# dacLayerBoard3.net
KiCad netlist of a schematic drawn in EAGLE
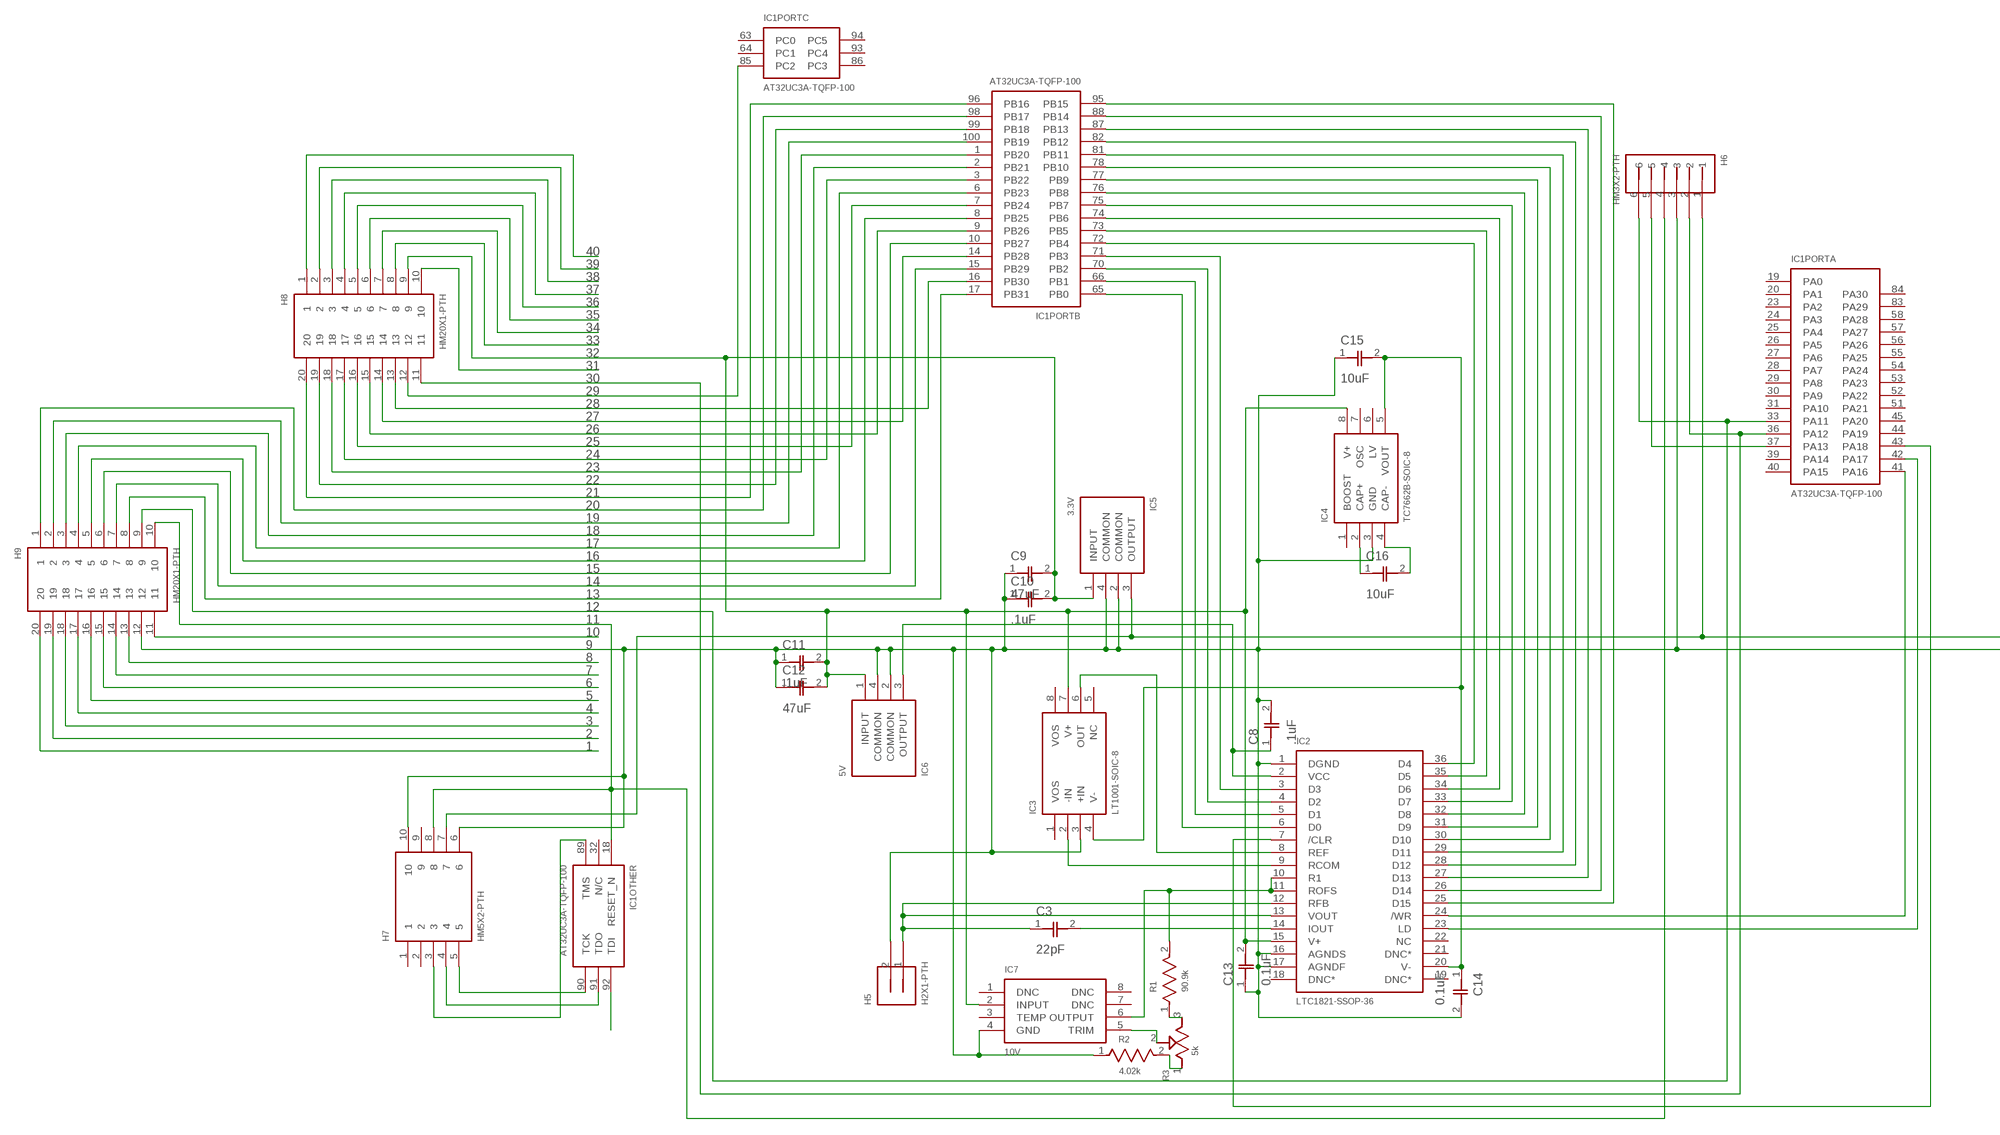
[diagram p0: schematic, sheet 1, part 1 of 2]
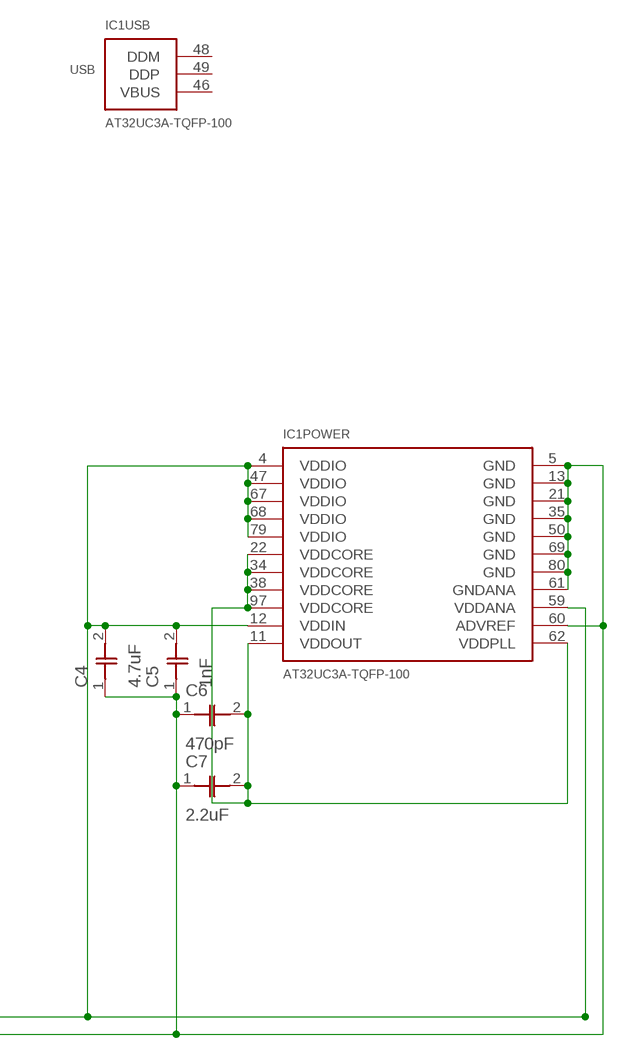
[diagram p1: schematic, sheet 1, part 2 of 2]

(export (version "E")
  (design (tool "Eeschema 10.0.6"))
  (components
    (comp (ref "C3")
      (value "22pF")
      (footprint "eagle-import:CAP-0603")
      (libsource (lib "eagle-import") (part "CAP-0603"))
    )
    (comp (ref "C4")
      (value "4.7uF")
      (footprint "eagle-import:CAP-0603")
      (libsource (lib "eagle-import") (part "CAP-0603"))
    )
    (comp (ref "C5")
      (value "1nF")
      (footprint "eagle-import:CAP-0603")
      (libsource (lib "eagle-import") (part "CAP-0603"))
    )
    (comp (ref "C6")
      (value "470pF")
      (footprint "eagle-import:CAP-0603")
      (libsource (lib "eagle-import") (part "CAP-0603"))
    )
    (comp (ref "C7")
      (value "2.2uF")
      (footprint "eagle-import:CAP-0603")
      (libsource (lib "eagle-import") (part "CAP-0603"))
    )
    (comp (ref "C8")
      (value ".1uF")
      (footprint "eagle-import:CAP-0603")
      (libsource (lib "eagle-import") (part "CAP-0603"))
    )
    (comp (ref "C9")
      (value "47uF")
      (footprint "eagle-import:CAP-0603")
      (libsource (lib "eagle-import") (part "CAP-0603"))
    )
    (comp (ref "C10")
      (value ".1uF")
      (footprint "eagle-import:CAP-0603")
      (libsource (lib "eagle-import") (part "CAP-0603"))
    )
    (comp (ref "C11")
      (value ".1uF")
      (footprint "eagle-import:CAP-0603")
      (libsource (lib "eagle-import") (part "CAP-0603"))
    )
    (comp (ref "C12")
      (value "47uF")
      (footprint "eagle-import:CAP-0603")
      (libsource (lib "eagle-import") (part "CAP-0603"))
    )
    (comp (ref "C13")
      (value "0.1uF")
      (footprint "eagle-import:CAP-0603")
      (libsource (lib "eagle-import") (part "CAP-0603"))
    )
    (comp (ref "C14")
      (value "0.1uF")
      (footprint "eagle-import:CAP-0603")
      (libsource (lib "eagle-import") (part "CAP-0603"))
    )
    (comp (ref "C15")
      (value "10uF")
      (footprint "eagle-import:0805")
      (libsource (lib "eagle-import") (part "CAP-0805"))
    )
    (comp (ref "C16")
      (value "10uF")
      (footprint "eagle-import:0805")
      (libsource (lib "eagle-import") (part "CAP-0805"))
    )
    (comp (ref "H5")
      (value "H2X1-PTH")
      (footprint "eagle-import:HM2X1-PTH")
      (libsource (lib "eagle-import") (part "H2X1-PTH"))
    )
    (comp (ref "H6")
      (value "HM3X2-PTH")
      (footprint "eagle-import:HM3X2-PTH")
      (libsource (lib "eagle-import") (part "HM3X2-PTH"))
    )
    (comp (ref "H7")
      (value "HM5X2-PTH")
      (footprint "eagle-import:HM5X2-PTH")
      (libsource (lib "eagle-import") (part "HM5X2-PTH"))
    )
    (comp (ref "H8")
      (value "HM20X1-PTH")
      (footprint "eagle-import:HM20X1-PTH")
      (libsource (lib "eagle-import") (part "HM20X1-PTH"))
    )
    (comp (ref "H9")
      (value "HM20X1-PTH")
      (footprint "eagle-import:HM20X1-PTH")
      (libsource (lib "eagle-import") (part "HM20X1-PTH"))
    )
    (comp (ref "IC1")
      (value "AT32UC3A-TQFP-100")
      (footprint "eagle-import:TQFP-100")
      (libsource (lib "eagle-import") (part "AT32UC3A-TQFP-100"))
    )
    (comp (ref "IC2")
      (value "LTC1821-SSOP-36")
      (footprint "eagle-import:SSOP-36")
      (libsource (lib "eagle-import") (part "LTC1821-SSOP-36"))
    )
    (comp (ref "IC3")
      (value "LT1001-SOIC-8")
      (footprint "eagle-import:SOIC-8")
      (libsource (lib "eagle-import") (part "LT1001-SOIC-8"))
    )
    (comp (ref "IC4")
      (value "TC7662B-SOIC-8")
      (footprint "eagle-import:SOIC-8")
      (libsource (lib "eagle-import") (part "TC7662B-SOIC-8"))
    )
    (comp (ref "IC5")
      (value "3.3V")
      (footprint "eagle-import:SOT-223-4")
      (libsource (lib "eagle-import") (part "UA78M-SOT-223-4"))
    )
    (comp (ref "IC6")
      (value "5V")
      (footprint "eagle-import:SOT-223-4")
      (libsource (lib "eagle-import") (part "UA78M-SOT-223-4"))
    )
    (comp (ref "IC7")
      (value "10V")
      (footprint "eagle-import:SOIC-8")
      (libsource (lib "eagle-import") (part "LT1019-SOIC-8"))
    )
    (comp (ref "R1")
      (value "90.9k")
      (footprint "eagle-import:RES-0603")
      (libsource (lib "eagle-import") (part "RESISTOR-0603"))
    )
    (comp (ref "R2")
      (value "4.02k")
      (footprint "eagle-import:RES-0603")
      (libsource (lib "eagle-import") (part "RESISTOR-0603"))
    )
    (comp (ref "R3")
      (value "5k")
      (footprint "eagle-import:3303W")
      (libsource (lib "eagle-import") (part "TRIMPOT-3303W"))
    )
  )
  (nets
    (net (code "1") (name "/1") (class "Default")
      (node (ref "H9") (pin "20") (pinfunction "20_20") (pintype "bidirectional"))
    )
    (net (code "2") (name "/2") (class "Default")
      (node (ref "H9") (pin "19") (pinfunction "19_19") (pintype "bidirectional"))
    )
    (net (code "3") (name "/3") (class "Default")
      (node (ref "H9") (pin "18") (pinfunction "18_18") (pintype "bidirectional"))
    )
    (net (code "4") (name "/4") (class "Default")
      (node (ref "H9") (pin "17") (pinfunction "17_17") (pintype "bidirectional"))
    )
    (net (code "5") (name "/5") (class "Default")
      (node (ref "H9") (pin "16") (pinfunction "16_16") (pintype "bidirectional"))
    )
    (net (code "6") (name "/6") (class "Default")
      (node (ref "H9") (pin "15") (pinfunction "15_15") (pintype "bidirectional"))
    )
    (net (code "7") (name "/7") (class "Default")
      (node (ref "H9") (pin "14") (pinfunction "14_14") (pintype "bidirectional"))
    )
    (net (code "8") (name "/8") (class "Default")
      (node (ref "H9") (pin "13") (pinfunction "13_13") (pintype "bidirectional"))
    )
    (net (code "9") (name "/9") (class "Default")
      (node (ref "C10") (pin "1") (pinfunction "1_1") (pintype "passive"))
      (node (ref "C11") (pin "1") (pinfunction "1_1") (pintype "passive"))
      (node (ref "C12") (pin "1") (pinfunction "1_1") (pintype "passive"))
      (node (ref "C13") (pin "1") (pinfunction "1_1") (pintype "passive"))
      (node (ref "C14") (pin "2") (pinfunction "2_2") (pintype "passive"))
      (node (ref "C15") (pin "1") (pinfunction "1_1") (pintype "passive"))
      (node (ref "C4") (pin "1") (pinfunction "1_1") (pintype "passive"))
      (node (ref "C5") (pin "1") (pinfunction "1_1") (pintype "passive"))
      (node (ref "C6") (pin "1") (pinfunction "1_1") (pintype "passive"))
      (node (ref "C7") (pin "1") (pinfunction "1_1") (pintype "passive"))
      (node (ref "C8") (pin "2") (pinfunction "2_2") (pintype "passive"))
      (node (ref "C9") (pin "1") (pinfunction "1_1") (pintype "passive"))
      (node (ref "H5") (pin "2") (pinfunction "2_2") (pintype "passive"))
      (node (ref "H6") (pin "3") (pinfunction "3_3") (pintype "passive"))
      (node (ref "H7") (pin "10") (pinfunction "10_10") (pintype "passive"))
      (node (ref "H7") (pin "6") (pinfunction "6_6") (pintype "passive"))
      (node (ref "H9") (pin "12") (pinfunction "12_12") (pintype "bidirectional"))
      (node (ref "IC1") (pin "13") (pinfunction "GND_13") (pintype "power_in"))
      (node (ref "IC1") (pin "21") (pinfunction "GND_21") (pintype "power_in"))
      (node (ref "IC1") (pin "35") (pinfunction "GND_35") (pintype "power_in"))
      (node (ref "IC1") (pin "5") (pinfunction "GND_5") (pintype "power_in"))
      (node (ref "IC1") (pin "50") (pinfunction "GND_50") (pintype "power_in"))
      (node (ref "IC1") (pin "60") (pinfunction "ADVREF_60") (pintype "bidirectional"))
      (node (ref "IC1") (pin "61") (pinfunction "GNDANA_61") (pintype "power_in"))
      (node (ref "IC1") (pin "69") (pinfunction "GND_69") (pintype "power_in"))
      (node (ref "IC1") (pin "80") (pinfunction "GND_80") (pintype "power_in"))
      (node (ref "IC2") (pin "1") (pinfunction "DGND_1") (pintype "power_in"))
      (node (ref "IC2") (pin "16") (pinfunction "AGNDS_16") (pintype "bidirectional"))
      (node (ref "IC2") (pin "17") (pinfunction "AGNDF_17") (pintype "bidirectional"))
      (node (ref "IC3") (pin "3") (pinfunction "+IN_3") (pintype "input"))
      (node (ref "IC4") (pin "3") (pinfunction "GND_3") (pintype "power_in"))
      (node (ref "IC5") (pin "2") (pinfunction "COMMON_2") (pintype "power_in"))
      (node (ref "IC5") (pin "4") (pinfunction "COMMON_4") (pintype "power_in"))
      (node (ref "IC6") (pin "2") (pinfunction "COMMON_2") (pintype "power_in"))
      (node (ref "IC6") (pin "4") (pinfunction "COMMON_4") (pintype "power_in"))
      (node (ref "IC7") (pin "4") (pinfunction "GND_4") (pintype "bidirectional"))
      (node (ref "R2") (pin "1") (pinfunction "1_1") (pintype "passive"))
    )
    (net (code "10") (name "/10") (class "Default")
      (node (ref "H9") (pin "11") (pinfunction "11_11") (pintype "bidirectional"))
    )
    (net (code "11") (name "/11") (class "Default")
      (node (ref "H6") (pin "4") (pinfunction "4_4") (pintype "passive"))
      (node (ref "H7") (pin "8") (pinfunction "8_8") (pintype "passive"))
      (node (ref "H9") (pin "10") (pinfunction "10_10") (pintype "bidirectional"))
      (node (ref "IC1") (pin "18") (pinfunction "RESET_N_18") (pintype "bidirectional"))
    )
    (net (code "12") (name "/12") (class "Default")
      (node (ref "H6") (pin "6") (pinfunction "6_6") (pintype "passive"))
      (node (ref "H9") (pin "9") (pinfunction "9_9") (pintype "bidirectional"))
      (node (ref "IC1") (pin "33") (pinfunction "PA11_33") (pintype "bidirectional"))
    )
    (net (code "13") (name "/13") (class "Default")
      (node (ref "H9") (pin "8") (pinfunction "8_8") (pintype "bidirectional"))
      (node (ref "IC1") (pin "17") (pinfunction "PB31_17") (pintype "bidirectional"))
    )
    (net (code "14") (name "/14") (class "Default")
      (node (ref "H9") (pin "7") (pinfunction "7_7") (pintype "bidirectional"))
      (node (ref "IC1") (pin "15") (pinfunction "PB29_15") (pintype "bidirectional"))
    )
    (net (code "15") (name "/15") (class "Default")
      (node (ref "H9") (pin "6") (pinfunction "6_6") (pintype "bidirectional"))
      (node (ref "IC1") (pin "10") (pinfunction "PB27_10") (pintype "bidirectional"))
    )
    (net (code "16") (name "/16") (class "Default")
      (node (ref "H9") (pin "5") (pinfunction "5_5") (pintype "bidirectional"))
      (node (ref "IC1") (pin "8") (pinfunction "PB25_8") (pintype "bidirectional"))
    )
    (net (code "17") (name "/17") (class "Default")
      (node (ref "H9") (pin "4") (pinfunction "4_4") (pintype "bidirectional"))
      (node (ref "IC1") (pin "6") (pinfunction "PB23_6") (pintype "bidirectional"))
    )
    (net (code "18") (name "/18") (class "Default")
      (node (ref "H9") (pin "3") (pinfunction "3_3") (pintype "bidirectional"))
      (node (ref "IC1") (pin "2") (pinfunction "PB21_2") (pintype "bidirectional"))
    )
    (net (code "19") (name "/19") (class "Default")
      (node (ref "H9") (pin "2") (pinfunction "2_2") (pintype "bidirectional"))
      (node (ref "IC1") (pin "100") (pinfunction "PB19_100") (pintype "bidirectional"))
    )
    (net (code "20") (name "/20") (class "Default")
      (node (ref "H9") (pin "1") (pinfunction "1_1") (pintype "bidirectional"))
      (node (ref "IC1") (pin "98") (pinfunction "PB17_98") (pintype "bidirectional"))
    )
    (net (code "21") (name "/21") (class "Default")
      (node (ref "H8") (pin "20") (pinfunction "20_20") (pintype "bidirectional"))
      (node (ref "IC1") (pin "96") (pinfunction "PB16_96") (pintype "bidirectional"))
    )
    (net (code "22") (name "/22") (class "Default")
      (node (ref "H8") (pin "19") (pinfunction "19_19") (pintype "bidirectional"))
      (node (ref "IC1") (pin "99") (pinfunction "PB18_99") (pintype "bidirectional"))
    )
    (net (code "23") (name "/23") (class "Default")
      (node (ref "H8") (pin "18") (pinfunction "18_18") (pintype "bidirectional"))
      (node (ref "IC1") (pin "1") (pinfunction "PB20_1") (pintype "bidirectional"))
    )
    (net (code "24") (name "/24") (class "Default")
      (node (ref "H8") (pin "17") (pinfunction "17_17") (pintype "bidirectional"))
      (node (ref "IC1") (pin "3") (pinfunction "PB22_3") (pintype "bidirectional"))
    )
    (net (code "25") (name "/25") (class "Default")
      (node (ref "H8") (pin "16") (pinfunction "16_16") (pintype "bidirectional"))
      (node (ref "IC1") (pin "7") (pinfunction "PB24_7") (pintype "bidirectional"))
    )
    (net (code "26") (name "/26") (class "Default")
      (node (ref "H8") (pin "15") (pinfunction "15_15") (pintype "bidirectional"))
      (node (ref "IC1") (pin "9") (pinfunction "PB26_9") (pintype "bidirectional"))
    )
    (net (code "27") (name "/27") (class "Default")
      (node (ref "H8") (pin "14") (pinfunction "14_14") (pintype "bidirectional"))
      (node (ref "IC1") (pin "14") (pinfunction "PB28_14") (pintype "bidirectional"))
    )
    (net (code "28") (name "/28") (class "Default")
      (node (ref "H8") (pin "13") (pinfunction "13_13") (pintype "bidirectional"))
      (node (ref "IC1") (pin "16") (pinfunction "PB30_16") (pintype "bidirectional"))
    )
    (net (code "29") (name "/29") (class "Default")
      (node (ref "H8") (pin "12") (pinfunction "12_12") (pintype "bidirectional"))
      (node (ref "IC1") (pin "85") (pinfunction "PC2_85") (pintype "bidirectional"))
    )
    (net (code "30") (name "/30") (class "Default")
      (node (ref "H6") (pin "2") (pinfunction "2_2") (pintype "passive"))
      (node (ref "H8") (pin "11") (pinfunction "11_11") (pintype "bidirectional"))
      (node (ref "IC1") (pin "36") (pinfunction "PA12_36") (pintype "bidirectional"))
    )
    (net (code "31") (name "/31") (class "Default")
      (node (ref "H8") (pin "10") (pinfunction "10_10") (pintype "bidirectional"))
    )
    (net (code "32") (name "/32") (class "Default")
      (node (ref "C10") (pin "2") (pinfunction "2_2") (pintype "passive"))
      (node (ref "C11") (pin "2") (pinfunction "2_2") (pintype "passive"))
      (node (ref "C12") (pin "2") (pinfunction "2_2") (pintype "passive"))
      (node (ref "C13") (pin "2") (pinfunction "2_2") (pintype "passive"))
      (node (ref "C9") (pin "2") (pinfunction "2_2") (pintype "passive"))
      (node (ref "H8") (pin "9") (pinfunction "9_9") (pintype "bidirectional"))
      (node (ref "IC2") (pin "15") (pinfunction "V+_15") (pintype "bidirectional"))
      (node (ref "IC3") (pin "7") (pinfunction "V+_7") (pintype "power_in"))
      (node (ref "IC4") (pin "8") (pinfunction "V+_8") (pintype "power_in"))
      (node (ref "IC5") (pin "1") (pinfunction "INPUT_1") (pintype "power_in"))
      (node (ref "IC6") (pin "1") (pinfunction "INPUT_1") (pintype "power_in"))
      (node (ref "IC7") (pin "2") (pinfunction "INPUT_2") (pintype "bidirectional"))
    )
    (net (code "33") (name "/33") (class "Default")
      (node (ref "H8") (pin "8") (pinfunction "8_8") (pintype "bidirectional"))
    )
    (net (code "34") (name "/34") (class "Default")
      (node (ref "H8") (pin "7") (pinfunction "7_7") (pintype "bidirectional"))
    )
    (net (code "35") (name "/35") (class "Default")
      (node (ref "H8") (pin "6") (pinfunction "6_6") (pintype "bidirectional"))
    )
    (net (code "36") (name "/36") (class "Default")
      (node (ref "H8") (pin "5") (pinfunction "5_5") (pintype "bidirectional"))
    )
    (net (code "37") (name "/37") (class "Default")
      (node (ref "H8") (pin "4") (pinfunction "4_4") (pintype "bidirectional"))
    )
    (net (code "38") (name "/38") (class "Default")
      (node (ref "H8") (pin "3") (pinfunction "3_3") (pintype "bidirectional"))
    )
    (net (code "39") (name "/39") (class "Default")
      (node (ref "H8") (pin "2") (pinfunction "2_2") (pintype "bidirectional"))
    )
    (net (code "40") (name "/40") (class "Default")
      (node (ref "H8") (pin "1") (pinfunction "1_1") (pintype "bidirectional"))
    )
    (net (code "41") (name "Net-(IC1A-TCK)") (class "Default")
      (node (ref "H7") (pin "5") (pinfunction "5_5") (pintype "passive"))
      (node (ref "IC1") (pin "90") (pinfunction "TCK_90") (pintype "bidirectional"))
    )
    (net (code "42") (name "Net-(IC1A-TDO)") (class "Default")
      (node (ref "H7") (pin "4") (pinfunction "4_4") (pintype "passive"))
      (node (ref "IC1") (pin "91") (pinfunction "TDO_91") (pintype "bidirectional"))
    )
    (net (code "43") (name "Net-(IC1A-TMS)") (class "Default")
      (node (ref "H7") (pin "3") (pinfunction "3_3") (pintype "passive"))
      (node (ref "IC1") (pin "89") (pinfunction "TMS_89") (pintype "bidirectional"))
    )
    (net (code "44") (name "Net-(IC1B-PA13)") (class "Default")
      (node (ref "H6") (pin "5") (pinfunction "5_5") (pintype "passive"))
      (node (ref "IC1") (pin "37") (pinfunction "PA13_37") (pintype "bidirectional"))
    )
    (net (code "45") (name "Net-(IC1B-PA16)") (class "Default")
      (node (ref "IC1") (pin "41") (pinfunction "PA16_41") (pintype "bidirectional"))
      (node (ref "IC2") (pin "24") (pinfunction "/WR_24") (pintype "bidirectional"))
    )
    (net (code "46") (name "Net-(IC1B-PA17)") (class "Default")
      (node (ref "IC1") (pin "42") (pinfunction "PA17_42") (pintype "bidirectional"))
      (node (ref "IC2") (pin "23") (pinfunction "LD_23") (pintype "bidirectional"))
    )
    (net (code "47") (name "Net-(IC1B-PA18)") (class "Default")
      (node (ref "IC1") (pin "43") (pinfunction "PA18_43") (pintype "bidirectional"))
      (node (ref "IC2") (pin "7") (pinfunction "/CLR_7") (pintype "input"))
    )
    (net (code "48") (name "Net-(IC1C-PB0)") (class "Default")
      (node (ref "IC1") (pin "65") (pinfunction "PB0_65") (pintype "bidirectional"))
      (node (ref "IC2") (pin "6") (pinfunction "D0_6") (pintype "input"))
    )
    (net (code "49") (name "Net-(IC1C-PB1)") (class "Default")
      (node (ref "IC1") (pin "66") (pinfunction "PB1_66") (pintype "bidirectional"))
      (node (ref "IC2") (pin "5") (pinfunction "D1_5") (pintype "input"))
    )
    (net (code "50") (name "Net-(IC1C-PB2)") (class "Default")
      (node (ref "IC1") (pin "70") (pinfunction "PB2_70") (pintype "bidirectional"))
      (node (ref "IC2") (pin "4") (pinfunction "D2_4") (pintype "input"))
    )
    (net (code "51") (name "Net-(IC1C-PB3)") (class "Default")
      (node (ref "IC1") (pin "71") (pinfunction "PB3_71") (pintype "bidirectional"))
      (node (ref "IC2") (pin "3") (pinfunction "D3_3") (pintype "input"))
    )
    (net (code "52") (name "Net-(IC1C-PB4)") (class "Default")
      (node (ref "IC1") (pin "72") (pinfunction "PB4_72") (pintype "bidirectional"))
      (node (ref "IC2") (pin "36") (pinfunction "D4_36") (pintype "bidirectional"))
    )
    (net (code "53") (name "Net-(IC1C-PB5)") (class "Default")
      (node (ref "IC1") (pin "73") (pinfunction "PB5_73") (pintype "bidirectional"))
      (node (ref "IC2") (pin "35") (pinfunction "D5_35") (pintype "bidirectional"))
    )
    (net (code "54") (name "Net-(IC1C-PB6)") (class "Default")
      (node (ref "IC1") (pin "74") (pinfunction "PB6_74") (pintype "bidirectional"))
      (node (ref "IC2") (pin "34") (pinfunction "D6_34") (pintype "bidirectional"))
    )
    (net (code "55") (name "Net-(IC1C-PB7)") (class "Default")
      (node (ref "IC1") (pin "75") (pinfunction "PB7_75") (pintype "bidirectional"))
      (node (ref "IC2") (pin "33") (pinfunction "D7_33") (pintype "bidirectional"))
    )
    (net (code "56") (name "Net-(IC1C-PB8)") (class "Default")
      (node (ref "IC1") (pin "76") (pinfunction "PB8_76") (pintype "bidirectional"))
      (node (ref "IC2") (pin "32") (pinfunction "D8_32") (pintype "bidirectional"))
    )
    (net (code "57") (name "Net-(IC1C-PB9)") (class "Default")
      (node (ref "IC1") (pin "77") (pinfunction "PB9_77") (pintype "bidirectional"))
      (node (ref "IC2") (pin "31") (pinfunction "D9_31") (pintype "bidirectional"))
    )
    (net (code "58") (name "Net-(IC1C-PB10)") (class "Default")
      (node (ref "IC1") (pin "78") (pinfunction "PB10_78") (pintype "bidirectional"))
      (node (ref "IC2") (pin "30") (pinfunction "D10_30") (pintype "bidirectional"))
    )
    (net (code "59") (name "Net-(IC1C-PB11)") (class "Default")
      (node (ref "IC1") (pin "81") (pinfunction "PB11_81") (pintype "bidirectional"))
      (node (ref "IC2") (pin "29") (pinfunction "D11_29") (pintype "bidirectional"))
    )
    (net (code "60") (name "Net-(IC1C-PB12)") (class "Default")
      (node (ref "IC1") (pin "82") (pinfunction "PB12_82") (pintype "bidirectional"))
      (node (ref "IC2") (pin "28") (pinfunction "D12_28") (pintype "bidirectional"))
    )
    (net (code "61") (name "Net-(IC1C-PB13)") (class "Default")
      (node (ref "IC1") (pin "87") (pinfunction "PB13_87") (pintype "bidirectional"))
      (node (ref "IC2") (pin "27") (pinfunction "D13_27") (pintype "bidirectional"))
    )
    (net (code "62") (name "Net-(IC1C-PB14)") (class "Default")
      (node (ref "IC1") (pin "88") (pinfunction "PB14_88") (pintype "bidirectional"))
      (node (ref "IC2") (pin "26") (pinfunction "D14_26") (pintype "bidirectional"))
    )
    (net (code "63") (name "Net-(IC1C-PB15)") (class "Default")
      (node (ref "IC1") (pin "95") (pinfunction "PB15_95") (pintype "bidirectional"))
      (node (ref "IC2") (pin "25") (pinfunction "D15_25") (pintype "bidirectional"))
    )
    (net (code "64") (name "Net-(IC1E-VDDANA)") (class "Default")
      (node (ref "C4") (pin "2") (pinfunction "2_2") (pintype "passive"))
      (node (ref "C5") (pin "2") (pinfunction "2_2") (pintype "passive"))
      (node (ref "H6") (pin "1") (pinfunction "1_1") (pintype "passive"))
      (node (ref "H7") (pin "7") (pinfunction "7_7") (pintype "passive"))
      (node (ref "IC1") (pin "12") (pinfunction "VDDIN_12") (pintype "input"))
      (node (ref "IC1") (pin "4") (pinfunction "VDDIO_4") (pintype "bidirectional"))
      (node (ref "IC1") (pin "47") (pinfunction "VDDIO_47") (pintype "bidirectional"))
      (node (ref "IC1") (pin "59") (pinfunction "VDDANA_59") (pintype "bidirectional"))
      (node (ref "IC1") (pin "67") (pinfunction "VDDIO_67") (pintype "bidirectional"))
      (node (ref "IC1") (pin "68") (pinfunction "VDDIO_68") (pintype "bidirectional"))
      (node (ref "IC1") (pin "79") (pinfunction "VDDIO_79") (pintype "bidirectional"))
      (node (ref "IC5") (pin "3") (pinfunction "OUTPUT_3") (pintype "power_in"))
    )
    (net (code "65") (name "Net-(IC1E-VDDOUT)") (class "Default")
      (node (ref "C6") (pin "2") (pinfunction "2_2") (pintype "passive"))
      (node (ref "C7") (pin "2") (pinfunction "2_2") (pintype "passive"))
      (node (ref "IC1") (pin "11") (pinfunction "VDDOUT_11") (pintype "output"))
      (node (ref "IC1") (pin "22") (pinfunction "VDDCORE_22") (pintype "bidirectional"))
      (node (ref "IC1") (pin "34") (pinfunction "VDDCORE_34") (pintype "bidirectional"))
      (node (ref "IC1") (pin "38") (pinfunction "VDDCORE_38") (pintype "bidirectional"))
      (node (ref "IC1") (pin "62") (pinfunction "VDDPLL_62") (pintype "bidirectional"))
      (node (ref "IC1") (pin "97") (pinfunction "VDDCORE_97") (pintype "bidirectional"))
    )
    (net (code "66") (name "Net-(IC2-IOUT)") (class "Default")
      (node (ref "C3") (pin "2") (pinfunction "2_2") (pintype "passive"))
      (node (ref "IC2") (pin "14") (pinfunction "IOUT_14") (pintype "output"))
    )
    (net (code "67") (name "Net-(IC2-R1)") (class "Default")
      (node (ref "IC2") (pin "10") (pinfunction "R1_10") (pintype "bidirectional"))
      (node (ref "IC2") (pin "11") (pinfunction "ROFS_11") (pintype "bidirectional"))
      (node (ref "IC7") (pin "6") (pinfunction "OUTPUT_6") (pintype "bidirectional"))
      (node (ref "R1") (pin "2") (pinfunction "2_2") (pintype "passive"))
    )
    (net (code "68") (name "Net-(IC2-RCOM)") (class "Default")
      (node (ref "IC2") (pin "9") (pinfunction "RCOM_9") (pintype "bidirectional"))
      (node (ref "IC3") (pin "2") (pinfunction "-IN_2") (pintype "input"))
    )
    (net (code "69") (name "Net-(IC2-REF)") (class "Default")
      (node (ref "IC2") (pin "8") (pinfunction "REF_8") (pintype "bidirectional"))
      (node (ref "IC3") (pin "6") (pinfunction "OUT_6") (pintype "output"))
    )
    (net (code "70") (name "Net-(IC2-RFB)") (class "Default")
      (node (ref "C3") (pin "1") (pinfunction "1_1") (pintype "passive"))
      (node (ref "H5") (pin "1") (pinfunction "1_1") (pintype "passive"))
      (node (ref "IC2") (pin "12") (pinfunction "RFB_12") (pintype "bidirectional"))
      (node (ref "IC2") (pin "13") (pinfunction "VOUT_13") (pintype "output"))
    )
    (net (code "71") (name "Net-(IC2-V-)") (class "Default")
      (node (ref "C14") (pin "1") (pinfunction "1_1") (pintype "passive"))
      (node (ref "C15") (pin "2") (pinfunction "2_2") (pintype "passive"))
      (node (ref "IC2") (pin "20") (pinfunction "V-_20") (pintype "bidirectional"))
      (node (ref "IC3") (pin "4") (pinfunction "V-_4") (pintype "power_in"))
      (node (ref "IC4") (pin "5") (pinfunction "VOUT_5") (pintype "power_in"))
    )
    (net (code "72") (name "Net-(IC2-VCC)") (class "Default")
      (node (ref "C8") (pin "1") (pinfunction "1_1") (pintype "passive"))
      (node (ref "IC2") (pin "2") (pinfunction "VCC_2") (pintype "power_in"))
      (node (ref "IC6") (pin "3") (pinfunction "OUTPUT_3") (pintype "power_in"))
    )
    (net (code "73") (name "Net-(IC4-CAP+)") (class "Default")
      (node (ref "C16") (pin "1") (pinfunction "1_1") (pintype "passive"))
      (node (ref "IC4") (pin "2") (pinfunction "CAP+_2") (pintype "passive"))
    )
    (net (code "74") (name "Net-(IC4-CAP-)") (class "Default")
      (node (ref "C16") (pin "2") (pinfunction "2_2") (pintype "passive"))
      (node (ref "IC4") (pin "4") (pinfunction "CAP-_4") (pintype "passive"))
    )
    (net (code "75") (name "Net-(IC7-TRIM)") (class "Default")
      (node (ref "IC7") (pin "5") (pinfunction "TRIM_5") (pintype "bidirectional"))
      (node (ref "R3") (pin "2") (pinfunction "2_2") (pintype "passive"))
    )
    (net (code "76") (name "Net-(R1-Pad1)") (class "Default")
      (node (ref "R1") (pin "1") (pinfunction "1_1") (pintype "passive"))
      (node (ref "R3") (pin "3") (pinfunction "3_3") (pintype "passive"))
    )
    (net (code "77") (name "Net-(R2-Pad2)") (class "Default")
      (node (ref "R2") (pin "2") (pinfunction "2_2") (pintype "passive"))
      (node (ref "R3") (pin "1") (pinfunction "1_1") (pintype "passive"))
    )
    (net (code "78") (name "unconnected-(H7-Pad1)") (class "Default")
      (node (ref "H7") (pin "1") (pinfunction "1_1") (pintype "passive"))
    )
    (net (code "79") (name "unconnected-(H7-Pad2)") (class "Default")
      (node (ref "H7") (pin "2") (pinfunction "2_2") (pintype "passive"))
    )
    (net (code "80") (name "unconnected-(H7-Pad9)") (class "Default")
      (node (ref "H7") (pin "9") (pinfunction "9_9") (pintype "passive"))
    )
    (net (code "81") (name "unconnected-(IC1A-N{slash}C-Pad32)") (class "Default")
      (node (ref "IC1") (pin "32") (pinfunction "N/C_32") (pintype "no_connect"))
    )
    (net (code "82") (name "unconnected-(IC1A-TDI-Pad92)") (class "Default")
      (node (ref "IC1") (pin "92") (pinfunction "TDI_92") (pintype "bidirectional"))
    )
    (net (code "83") (name "unconnected-(IC1B-PA0-Pad19)") (class "Default")
      (node (ref "IC1") (pin "19") (pinfunction "PA0_19") (pintype "bidirectional"))
    )
    (net (code "84") (name "unconnected-(IC1B-PA1-Pad20)") (class "Default")
      (node (ref "IC1") (pin "20") (pinfunction "PA1_20") (pintype "bidirectional"))
    )
    (net (code "85") (name "unconnected-(IC1B-PA2-Pad23)") (class "Default")
      (node (ref "IC1") (pin "23") (pinfunction "PA2_23") (pintype "bidirectional"))
    )
    (net (code "86") (name "unconnected-(IC1B-PA3-Pad24)") (class "Default")
      (node (ref "IC1") (pin "24") (pinfunction "PA3_24") (pintype "bidirectional"))
    )
    (net (code "87") (name "unconnected-(IC1B-PA4-Pad25)") (class "Default")
      (node (ref "IC1") (pin "25") (pinfunction "PA4_25") (pintype "bidirectional"))
    )
    (net (code "88") (name "unconnected-(IC1B-PA5-Pad26)") (class "Default")
      (node (ref "IC1") (pin "26") (pinfunction "PA5_26") (pintype "bidirectional"))
    )
    (net (code "89") (name "unconnected-(IC1B-PA6-Pad27)") (class "Default")
      (node (ref "IC1") (pin "27") (pinfunction "PA6_27") (pintype "bidirectional"))
    )
    (net (code "90") (name "unconnected-(IC1B-PA7-Pad28)") (class "Default")
      (node (ref "IC1") (pin "28") (pinfunction "PA7_28") (pintype "bidirectional"))
    )
    (net (code "91") (name "unconnected-(IC1B-PA8-Pad29)") (class "Default")
      (node (ref "IC1") (pin "29") (pinfunction "PA8_29") (pintype "bidirectional"))
    )
    (net (code "92") (name "unconnected-(IC1B-PA9-Pad30)") (class "Default")
      (node (ref "IC1") (pin "30") (pinfunction "PA9_30") (pintype "bidirectional"))
    )
    (net (code "93") (name "unconnected-(IC1B-PA10-Pad31)") (class "Default")
      (node (ref "IC1") (pin "31") (pinfunction "PA10_31") (pintype "bidirectional"))
    )
    (net (code "94") (name "unconnected-(IC1B-PA14-Pad39)") (class "Default")
      (node (ref "IC1") (pin "39") (pinfunction "PA14_39") (pintype "bidirectional"))
    )
    (net (code "95") (name "unconnected-(IC1B-PA15-Pad40)") (class "Default")
      (node (ref "IC1") (pin "40") (pinfunction "PA15_40") (pintype "bidirectional"))
    )
    (net (code "96") (name "unconnected-(IC1B-PA19-Pad44)") (class "Default")
      (node (ref "IC1") (pin "44") (pinfunction "PA19_44") (pintype "bidirectional"))
    )
    (net (code "97") (name "unconnected-(IC1B-PA20-Pad45)") (class "Default")
      (node (ref "IC1") (pin "45") (pinfunction "PA20_45") (pintype "bidirectional"))
    )
    (net (code "98") (name "unconnected-(IC1B-PA21-Pad51)") (class "Default")
      (node (ref "IC1") (pin "51") (pinfunction "PA21_51") (pintype "bidirectional"))
    )
    (net (code "99") (name "unconnected-(IC1B-PA22-Pad52)") (class "Default")
      (node (ref "IC1") (pin "52") (pinfunction "PA22_52") (pintype "bidirectional"))
    )
    (net (code "100") (name "unconnected-(IC1B-PA23-Pad53)") (class "Default")
      (node (ref "IC1") (pin "53") (pinfunction "PA23_53") (pintype "bidirectional"))
    )
    (net (code "101") (name "unconnected-(IC1B-PA24-Pad54)") (class "Default")
      (node (ref "IC1") (pin "54") (pinfunction "PA24_54") (pintype "bidirectional"))
    )
    (net (code "102") (name "unconnected-(IC1B-PA25-Pad55)") (class "Default")
      (node (ref "IC1") (pin "55") (pinfunction "PA25_55") (pintype "bidirectional"))
    )
    (net (code "103") (name "unconnected-(IC1B-PA26-Pad56)") (class "Default")
      (node (ref "IC1") (pin "56") (pinfunction "PA26_56") (pintype "bidirectional"))
    )
    (net (code "104") (name "unconnected-(IC1B-PA27-Pad57)") (class "Default")
      (node (ref "IC1") (pin "57") (pinfunction "PA27_57") (pintype "bidirectional"))
    )
    (net (code "105") (name "unconnected-(IC1B-PA28-Pad58)") (class "Default")
      (node (ref "IC1") (pin "58") (pinfunction "PA28_58") (pintype "bidirectional"))
    )
    (net (code "106") (name "unconnected-(IC1B-PA29-Pad83)") (class "Default")
      (node (ref "IC1") (pin "83") (pinfunction "PA29_83") (pintype "bidirectional"))
    )
    (net (code "107") (name "unconnected-(IC1B-PA30-Pad84)") (class "Default")
      (node (ref "IC1") (pin "84") (pinfunction "PA30_84") (pintype "bidirectional"))
    )
    (net (code "108") (name "unconnected-(IC1D-PC0-Pad63)") (class "Default")
      (node (ref "IC1") (pin "63") (pinfunction "PC0_63") (pintype "bidirectional"))
    )
    (net (code "109") (name "unconnected-(IC1D-PC1-Pad64)") (class "Default")
      (node (ref "IC1") (pin "64") (pinfunction "PC1_64") (pintype "bidirectional"))
    )
    (net (code "110") (name "unconnected-(IC1D-PC3-Pad86)") (class "Default")
      (node (ref "IC1") (pin "86") (pinfunction "PC3_86") (pintype "bidirectional"))
    )
    (net (code "111") (name "unconnected-(IC1D-PC4-Pad93)") (class "Default")
      (node (ref "IC1") (pin "93") (pinfunction "PC4_93") (pintype "bidirectional"))
    )
    (net (code "112") (name "unconnected-(IC1D-PC5-Pad94)") (class "Default")
      (node (ref "IC1") (pin "94") (pinfunction "PC5_94") (pintype "bidirectional"))
    )
    (net (code "113") (name "unconnected-(IC1F-DDM-Pad48)") (class "Default")
      (node (ref "IC1") (pin "48") (pinfunction "DDM_48") (pintype "bidirectional"))
    )
    (net (code "114") (name "unconnected-(IC1F-DDP-Pad49)") (class "Default")
      (node (ref "IC1") (pin "49") (pinfunction "DDP_49") (pintype "bidirectional"))
    )
    (net (code "115") (name "unconnected-(IC1F-VBUS-Pad46)") (class "Default")
      (node (ref "IC1") (pin "46") (pinfunction "VBUS_46") (pintype "bidirectional"))
    )
    (net (code "116") (name "unconnected-(IC2-DNC*-Pad18)") (class "Default")
      (node (ref "IC2") (pin "18") (pinfunction "DNC*_18") (pintype "bidirectional"))
    )
    (net (code "117") (name "unconnected-(IC2-DNC*-Pad19)") (class "Default")
      (node (ref "IC2") (pin "19") (pinfunction "DNC*_19") (pintype "bidirectional"))
    )
    (net (code "118") (name "unconnected-(IC2-DNC*-Pad21)") (class "Default")
      (node (ref "IC2") (pin "21") (pinfunction "DNC*_21") (pintype "bidirectional"))
    )
    (net (code "119") (name "unconnected-(IC2-NC-Pad22)") (class "Default")
      (node (ref "IC2") (pin "22") (pinfunction "NC_22") (pintype "bidirectional"))
    )
    (net (code "120") (name "unconnected-(IC3-NC-Pad5)") (class "Default")
      (node (ref "IC3") (pin "5") (pinfunction "NC_5") (pintype "no_connect"))
    )
    (net (code "121") (name "unconnected-(IC3-VOS-Pad1)") (class "Default")
      (node (ref "IC3") (pin "1") (pinfunction "VOS_1") (pintype "input"))
    )
    (net (code "122") (name "unconnected-(IC3-VOS-Pad8)") (class "Default")
      (node (ref "IC3") (pin "8") (pinfunction "VOS_8") (pintype "input"))
    )
    (net (code "123") (name "unconnected-(IC4-BOOST-Pad1)") (class "Default")
      (node (ref "IC4") (pin "1") (pinfunction "BOOST_1") (pintype "input"))
    )
    (net (code "124") (name "unconnected-(IC4-LV-Pad6)") (class "Default")
      (node (ref "IC4") (pin "6") (pinfunction "LV_6") (pintype "input"))
    )
    (net (code "125") (name "unconnected-(IC4-OSC-Pad7)") (class "Default")
      (node (ref "IC4") (pin "7") (pinfunction "OSC_7") (pintype "passive"))
    )
    (net (code "126") (name "unconnected-(IC7-DNC-Pad1)") (class "Default")
      (node (ref "IC7") (pin "1") (pinfunction "DNC_1") (pintype "bidirectional"))
    )
    (net (code "127") (name "unconnected-(IC7-DNC-Pad7)") (class "Default")
      (node (ref "IC7") (pin "7") (pinfunction "DNC_7") (pintype "bidirectional"))
    )
    (net (code "128") (name "unconnected-(IC7-DNC-Pad8)") (class "Default")
      (node (ref "IC7") (pin "8") (pinfunction "DNC_8") (pintype "bidirectional"))
    )
    (net (code "129") (name "unconnected-(IC7-TEMP-Pad3)") (class "Default")
      (node (ref "IC7") (pin "3") (pinfunction "TEMP_3") (pintype "bidirectional"))
    )
  )
)
